# Addon_-_out8_16A_-_energy_storage_-_4TE_.net
KiCad netlist of a schematic drawn in EAGLE
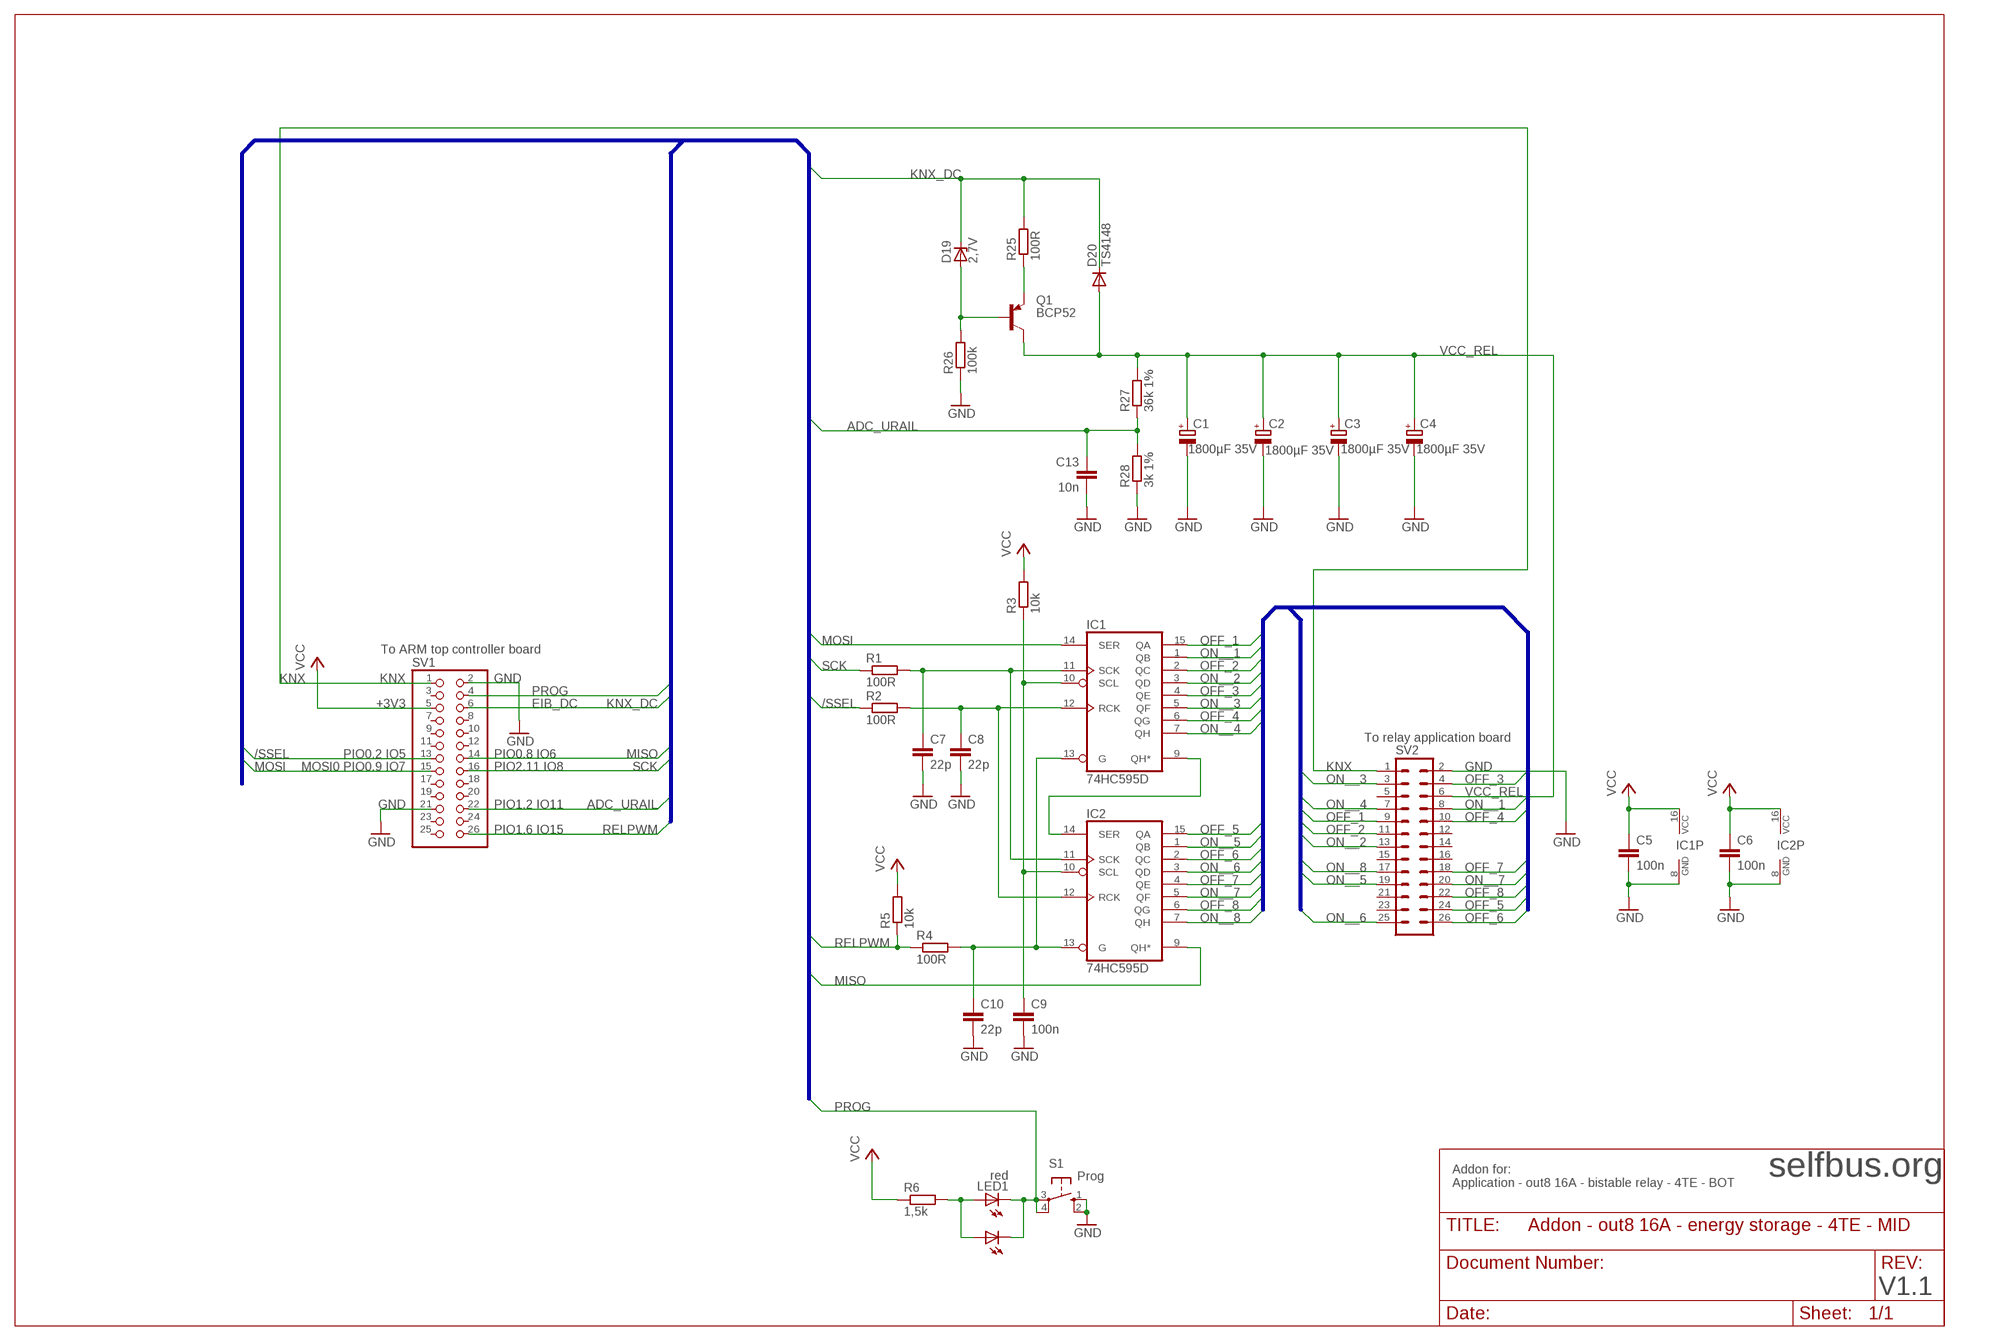
[diagram p0: schematic, sheet 1]

(export (version "E")
  (design (tool "Eeschema 10.0.6"))
  (components
    (comp (ref "C1")
      (value "1800µF 35V")
      (footprint "eagle-import:E5-13-30")
      (libsource (lib "eagle-import") (part "CPOL-EUE5-13-30"))
    )
    (comp (ref "C2")
      (value "1800µF 35V")
      (footprint "eagle-import:E5-13-30")
      (libsource (lib "eagle-import") (part "CPOL-EUE5-13-30"))
    )
    (comp (ref "C3")
      (value "1800µF 35V")
      (footprint "eagle-import:E5-13-30")
      (libsource (lib "eagle-import") (part "CPOL-EUE5-13-30"))
    )
    (comp (ref "C4")
      (value "1800µF 35V")
      (footprint "eagle-import:E5-13-30")
      (libsource (lib "eagle-import") (part "CPOL-EUE5-13-30"))
    )
    (comp (ref "C5")
      (value "100n")
      (footprint "eagle-import:R0805M")
      (libsource (lib "eagle-import") (part "C-EUC0805M"))
    )
    (comp (ref "C6")
      (value "100n")
      (footprint "eagle-import:R0805M")
      (libsource (lib "eagle-import") (part "C-EUC0805M"))
    )
    (comp (ref "C7")
      (value "22p")
      (footprint "eagle-import:R0805M")
      (libsource (lib "eagle-import") (part "C-EUC0805M"))
    )
    (comp (ref "C8")
      (value "22p")
      (footprint "eagle-import:R0805M")
      (libsource (lib "eagle-import") (part "C-EUC0805M"))
    )
    (comp (ref "C9")
      (value "100n")
      (footprint "eagle-import:R0805M")
      (libsource (lib "eagle-import") (part "C-EUC0805M"))
    )
    (comp (ref "C10")
      (value "22p")
      (footprint "eagle-import:R0805M")
      (libsource (lib "eagle-import") (part "C-EUC0805M"))
    )
    (comp (ref "C13")
      (value "10n")
      (footprint "eagle-import:R0805M")
      (libsource (lib "eagle-import") (part "C-EUC0805M"))
    )
    (comp (ref "D19")
      (value "2,7V")
      (footprint "eagle-import:SOT23")
      (libsource (lib "eagle-import") (part "ZENER-DIODESOT23"))
    )
    (comp (ref "D20")
      (value "TS4148")
      (footprint "eagle-import:D0805")
      (libsource (lib "eagle-import") (part "DIODE-D0805"))
    )
    (comp (ref "IC1")
      (value "74HC595D")
      (footprint "eagle-import:SO16")
      (libsource (lib "eagle-import") (part "74595DHC"))
    )
    (comp (ref "IC2")
      (value "74HC595D")
      (footprint "eagle-import:SO16")
      (libsource (lib "eagle-import") (part "74595DHC"))
    )
    (comp (ref "LED1")
      (value "red")
      (footprint "eagle-import:LED3MM")
      (libsource (lib "eagle-import") (part "LED3MM"))
    )
    (comp (ref "LED2")
      (value "LG_T679-E1F1-1")
      (footprint "eagle-import:PLCC2")
      (libsource (lib "eagle-import") (part "_T679-?-1E1F1LG"))
    )
    (comp (ref "Q1")
      (value "BCP52")
      (footprint "eagle-import:SOT223")
      (libsource (lib "eagle-import") (part "FZT753SMD"))
    )
    (comp (ref "R1")
      (value "100R")
      (footprint "eagle-import:R0805M")
      (libsource (lib "eagle-import") (part "R-EU_R0805M"))
    )
    (comp (ref "R2")
      (value "100R")
      (footprint "eagle-import:R0805M")
      (libsource (lib "eagle-import") (part "R-EU_R0805M"))
    )
    (comp (ref "R3")
      (value "10k")
      (footprint "eagle-import:R0805M")
      (libsource (lib "eagle-import") (part "R-EU_R0805M"))
    )
    (comp (ref "R4")
      (value "100R")
      (footprint "eagle-import:R0805M")
      (libsource (lib "eagle-import") (part "R-EU_R0805M"))
    )
    (comp (ref "R5")
      (value "10k")
      (footprint "eagle-import:R0805M")
      (libsource (lib "eagle-import") (part "R-EU_R0805M"))
    )
    (comp (ref "R6")
      (value "1,5k")
      (footprint "eagle-import:R0805M")
      (libsource (lib "eagle-import") (part "R-EU_R0805M"))
    )
    (comp (ref "R25")
      (value "100R")
      (footprint "eagle-import:R0805M")
      (libsource (lib "eagle-import") (part "R-EU_R0805M"))
    )
    (comp (ref "R26")
      (value "100k")
      (footprint "eagle-import:R0805M")
      (libsource (lib "eagle-import") (part "R-EU_R0805M"))
    )
    (comp (ref "R27")
      (value "36k 1%")
      (footprint "eagle-import:R0805M")
      (libsource (lib "eagle-import") (part "R-EU_R0805M"))
    )
    (comp (ref "R28")
      (value "3k 1%")
      (footprint "eagle-import:R0805M")
      (libsource (lib "eagle-import") (part "R-EU_R0805M"))
    )
    (comp (ref "S1")
      (value "Prog")
      (footprint "eagle-import:B3F-10XX")
      (libsource (lib "eagle-import") (part "10-XX"))
    )
    (comp (ref "SV1")
      (value "B")
      (footprint "eagle-import:2X13SMD")
      (libsource (lib "eagle-import") (part "PINHD-2X13SMD"))
    )
    (comp (ref "SV2")
      (value "A")
      (footprint "eagle-import:ML26")
      (libsource (lib "eagle-import") (part "ML26"))
    )
  )
  (nets
    (net (code "1") (name "/ADC_URAIL") (class "Default")
      (node (ref "C13") (pin "1") (pinfunction "1_1") (pintype "passive"))
      (node (ref "R27") (pin "1") (pinfunction "1_1") (pintype "passive"))
      (node (ref "R28") (pin "2") (pinfunction "2_2") (pintype "passive"))
      (node (ref "SV1") (pin "22") (pinfunction "22_22") (pintype "passive"))
    )
    (net (code "2") (name "/KNX") (class "Default")
      (node (ref "SV1") (pin "1") (pinfunction "1_1") (pintype "passive"))
      (node (ref "SV2") (pin "1") (pinfunction "1_1") (pintype "passive"))
    )
    (net (code "3") (name "/KNX_DC") (class "Default")
      (node (ref "D19") (pin "3") (pinfunction "C_3") (pintype "passive"))
      (node (ref "D20") (pin "C") (pinfunction "C_C") (pintype "passive"))
      (node (ref "R25") (pin "2") (pinfunction "2_2") (pintype "passive"))
      (node (ref "SV1") (pin "6") (pinfunction "6_6") (pintype "passive"))
    )
    (net (code "4") (name "/MISO") (class "Default")
      (node (ref "IC2") (pin "9") (pinfunction "QH*_9") (pintype "tri_state"))
      (node (ref "SV1") (pin "14") (pinfunction "14_14") (pintype "passive"))
    )
    (net (code "5") (name "/MOSI") (class "Default")
      (node (ref "IC1") (pin "14") (pinfunction "SER_14") (pintype "input"))
      (node (ref "SV1") (pin "15") (pinfunction "15_15") (pintype "passive"))
    )
    (net (code "6") (name "/OFF_1") (class "Default")
      (node (ref "IC1") (pin "15") (pinfunction "QA_15") (pintype "tri_state"))
      (node (ref "SV2") (pin "9") (pinfunction "9_9") (pintype "passive"))
    )
    (net (code "7") (name "/OFF_2") (class "Default")
      (node (ref "IC1") (pin "2") (pinfunction "QC_2") (pintype "tri_state"))
      (node (ref "SV2") (pin "11") (pinfunction "11_11") (pintype "passive"))
    )
    (net (code "8") (name "/OFF_3") (class "Default")
      (node (ref "IC1") (pin "4") (pinfunction "QE_4") (pintype "tri_state"))
      (node (ref "SV2") (pin "4") (pinfunction "4_4") (pintype "passive"))
    )
    (net (code "9") (name "/OFF_4") (class "Default")
      (node (ref "IC1") (pin "6") (pinfunction "QG_6") (pintype "tri_state"))
      (node (ref "SV2") (pin "10") (pinfunction "10_10") (pintype "passive"))
    )
    (net (code "10") (name "/OFF_5") (class "Default")
      (node (ref "IC2") (pin "15") (pinfunction "QA_15") (pintype "tri_state"))
      (node (ref "SV2") (pin "24") (pinfunction "24_24") (pintype "passive"))
    )
    (net (code "11") (name "/OFF_6") (class "Default")
      (node (ref "IC2") (pin "2") (pinfunction "QC_2") (pintype "tri_state"))
      (node (ref "SV2") (pin "26") (pinfunction "26_26") (pintype "passive"))
    )
    (net (code "12") (name "/OFF_7") (class "Default")
      (node (ref "IC2") (pin "4") (pinfunction "QE_4") (pintype "tri_state"))
      (node (ref "SV2") (pin "18") (pinfunction "18_18") (pintype "passive"))
    )
    (net (code "13") (name "/OFF_8") (class "Default")
      (node (ref "IC2") (pin "6") (pinfunction "QG_6") (pintype "tri_state"))
      (node (ref "SV2") (pin "22") (pinfunction "22_22") (pintype "passive"))
    )
    (net (code "14") (name "/ON__1") (class "Default")
      (node (ref "IC1") (pin "1") (pinfunction "QB_1") (pintype "tri_state"))
      (node (ref "SV2") (pin "8") (pinfunction "8_8") (pintype "passive"))
    )
    (net (code "15") (name "/ON__2") (class "Default")
      (node (ref "IC1") (pin "3") (pinfunction "QD_3") (pintype "tri_state"))
      (node (ref "SV2") (pin "13") (pinfunction "13_13") (pintype "passive"))
    )
    (net (code "16") (name "/ON__3") (class "Default")
      (node (ref "IC1") (pin "5") (pinfunction "QF_5") (pintype "tri_state"))
      (node (ref "SV2") (pin "3") (pinfunction "3_3") (pintype "passive"))
    )
    (net (code "17") (name "/ON__4") (class "Default")
      (node (ref "IC1") (pin "7") (pinfunction "QH_7") (pintype "tri_state"))
      (node (ref "SV2") (pin "7") (pinfunction "7_7") (pintype "passive"))
    )
    (net (code "18") (name "/ON__5") (class "Default")
      (node (ref "IC2") (pin "1") (pinfunction "QB_1") (pintype "tri_state"))
      (node (ref "SV2") (pin "19") (pinfunction "19_19") (pintype "passive"))
    )
    (net (code "19") (name "/ON__6") (class "Default")
      (node (ref "IC2") (pin "3") (pinfunction "QD_3") (pintype "tri_state"))
      (node (ref "SV2") (pin "25") (pinfunction "25_25") (pintype "passive"))
    )
    (net (code "20") (name "/ON__7") (class "Default")
      (node (ref "IC2") (pin "5") (pinfunction "QF_5") (pintype "tri_state"))
      (node (ref "SV2") (pin "20") (pinfunction "20_20") (pintype "passive"))
    )
    (net (code "21") (name "/ON__8") (class "Default")
      (node (ref "IC2") (pin "7") (pinfunction "QH_7") (pintype "tri_state"))
      (node (ref "SV2") (pin "17") (pinfunction "17_17") (pintype "passive"))
    )
    (net (code "22") (name "/PROG") (class "Default")
      (node (ref "LED1") (pin "K") (pinfunction "C_K") (pintype "passive"))
      (node (ref "LED2") (pin "C") (pinfunction "C_C") (pintype "passive"))
      (node (ref "S1") (pin "3") (pinfunction "P_3") (pintype "passive"))
      (node (ref "S1") (pin "4") (pinfunction "P1_4") (pintype "passive"))
      (node (ref "SV1") (pin "4") (pinfunction "4_4") (pintype "passive"))
    )
    (net (code "23") (name "/RELPWM") (class "Default")
      (node (ref "R4") (pin "1") (pinfunction "1_1") (pintype "passive"))
      (node (ref "R5") (pin "1") (pinfunction "1_1") (pintype "passive"))
      (node (ref "SV1") (pin "26") (pinfunction "26_26") (pintype "passive"))
    )
    (net (code "24") (name "/SCK") (class "Default")
      (node (ref "R1") (pin "1") (pinfunction "1_1") (pintype "passive"))
      (node (ref "SV1") (pin "16") (pinfunction "16_16") (pintype "passive"))
    )
    (net (code "25") (name "/VCC_REL") (class "Default")
      (node (ref "C1") (pin "+") (pinfunction "+_+") (pintype "passive"))
      (node (ref "C2") (pin "+") (pinfunction "+_+") (pintype "passive"))
      (node (ref "C3") (pin "+") (pinfunction "+_+") (pintype "passive"))
      (node (ref "C4") (pin "+") (pinfunction "+_+") (pintype "passive"))
      (node (ref "D20") (pin "A") (pinfunction "A_A") (pintype "passive"))
      (node (ref "Q1") (pin "2") (pinfunction "C_2") (pintype "passive"))
      (node (ref "Q1") (pin "4") (pinfunction "C_4") (pintype "passive"))
      (node (ref "R27") (pin "2") (pinfunction "2_2") (pintype "passive"))
      (node (ref "SV2") (pin "6") (pinfunction "6_6") (pintype "passive"))
    )
    (net (code "26") (name "/{slash}SSEL") (class "Default")
      (node (ref "R2") (pin "1") (pinfunction "1_1") (pintype "passive"))
      (node (ref "SV1") (pin "13") (pinfunction "13_13") (pintype "passive"))
    )
    (net (code "27") (name "GND") (class "Default")
      (node (ref "C1") (pin "-") (pinfunction "-_-") (pintype "passive"))
      (node (ref "C10") (pin "2") (pinfunction "2_2") (pintype "passive"))
      (node (ref "C13") (pin "2") (pinfunction "2_2") (pintype "passive"))
      (node (ref "C2") (pin "-") (pinfunction "-_-") (pintype "passive"))
      (node (ref "C3") (pin "-") (pinfunction "-_-") (pintype "passive"))
      (node (ref "C4") (pin "-") (pinfunction "-_-") (pintype "passive"))
      (node (ref "C5") (pin "2") (pinfunction "2_2") (pintype "passive"))
      (node (ref "C6") (pin "2") (pinfunction "2_2") (pintype "passive"))
      (node (ref "C7") (pin "2") (pinfunction "2_2") (pintype "passive"))
      (node (ref "C8") (pin "2") (pinfunction "2_2") (pintype "passive"))
      (node (ref "C9") (pin "2") (pinfunction "2_2") (pintype "passive"))
      (node (ref "IC1") (pin "8") (pinfunction "GND_8") (pintype "power_in"))
      (node (ref "IC2") (pin "8") (pinfunction "GND_8") (pintype "power_in"))
      (node (ref "R26") (pin "1") (pinfunction "1_1") (pintype "passive"))
      (node (ref "R28") (pin "1") (pinfunction "1_1") (pintype "passive"))
      (node (ref "S1") (pin "1") (pinfunction "S_1") (pintype "passive"))
      (node (ref "S1") (pin "2") (pinfunction "S1_2") (pintype "passive"))
      (node (ref "SV1") (pin "2") (pinfunction "2_2") (pintype "passive"))
      (node (ref "SV1") (pin "21") (pinfunction "21_21") (pintype "passive"))
      (node (ref "SV2") (pin "2") (pinfunction "2_2") (pintype "passive"))
    )
    (net (code "28") (name "Net-(D19-A)") (class "Default")
      (node (ref "D19") (pin "1") (pinfunction "A_1") (pintype "passive"))
      (node (ref "Q1") (pin "1") (pinfunction "B_1") (pintype "passive"))
      (node (ref "R26") (pin "2") (pinfunction "2_2") (pintype "passive"))
    )
    (net (code "29") (name "Net-(IC1A-G)") (class "Default")
      (node (ref "C10") (pin "1") (pinfunction "1_1") (pintype "passive"))
      (node (ref "IC1") (pin "13") (pinfunction "G_13") (pintype "input"))
      (node (ref "IC2") (pin "13") (pinfunction "G_13") (pintype "input"))
      (node (ref "R4") (pin "2") (pinfunction "2_2") (pintype "passive"))
    )
    (net (code "30") (name "Net-(IC1A-QH*)") (class "Default")
      (node (ref "IC1") (pin "9") (pinfunction "QH*_9") (pintype "tri_state"))
      (node (ref "IC2") (pin "14") (pinfunction "SER_14") (pintype "input"))
    )
    (net (code "31") (name "Net-(IC1A-RCK)") (class "Default")
      (node (ref "C8") (pin "1") (pinfunction "1_1") (pintype "passive"))
      (node (ref "IC1") (pin "12") (pinfunction "RCK_12") (pintype "input"))
      (node (ref "IC2") (pin "12") (pinfunction "RCK_12") (pintype "input"))
      (node (ref "R2") (pin "2") (pinfunction "2_2") (pintype "passive"))
    )
    (net (code "32") (name "Net-(IC1A-SCK)") (class "Default")
      (node (ref "C7") (pin "1") (pinfunction "1_1") (pintype "passive"))
      (node (ref "IC1") (pin "11") (pinfunction "SCK_11") (pintype "input"))
      (node (ref "IC2") (pin "11") (pinfunction "SCK_11") (pintype "input"))
      (node (ref "R1") (pin "2") (pinfunction "2_2") (pintype "passive"))
    )
    (net (code "33") (name "Net-(IC1A-SCL)") (class "Default")
      (node (ref "C9") (pin "1") (pinfunction "1_1") (pintype "passive"))
      (node (ref "IC1") (pin "10") (pinfunction "SCL_10") (pintype "input"))
      (node (ref "IC2") (pin "10") (pinfunction "SCL_10") (pintype "input"))
      (node (ref "R3") (pin "1") (pinfunction "1_1") (pintype "passive"))
    )
    (net (code "34") (name "Net-(LED1-PadA)") (class "Default")
      (node (ref "LED1") (pin "A") (pinfunction "A_A") (pintype "passive"))
      (node (ref "LED2") (pin "A") (pinfunction "A_A") (pintype "passive"))
      (node (ref "R6") (pin "2") (pinfunction "2_2") (pintype "passive"))
    )
    (net (code "35") (name "Net-(Q1-E)") (class "Default")
      (node (ref "Q1") (pin "3") (pinfunction "E_3") (pintype "passive"))
      (node (ref "R25") (pin "1") (pinfunction "1_1") (pintype "passive"))
    )
    (net (code "36") (name "VCC") (class "Default")
      (node (ref "C5") (pin "1") (pinfunction "1_1") (pintype "passive"))
      (node (ref "C6") (pin "1") (pinfunction "1_1") (pintype "passive"))
      (node (ref "IC1") (pin "16") (pinfunction "VCC_16") (pintype "power_in"))
      (node (ref "IC2") (pin "16") (pinfunction "VCC_16") (pintype "power_in"))
      (node (ref "R3") (pin "2") (pinfunction "2_2") (pintype "passive"))
      (node (ref "R5") (pin "2") (pinfunction "2_2") (pintype "passive"))
      (node (ref "R6") (pin "1") (pinfunction "1_1") (pintype "passive"))
      (node (ref "SV1") (pin "5") (pinfunction "5_5") (pintype "passive"))
    )
    (net (code "37") (name "unconnected-(SV1-Pad3)") (class "Default")
      (node (ref "SV1") (pin "3") (pinfunction "3_3") (pintype "passive"))
    )
    (net (code "38") (name "unconnected-(SV1-Pad7)") (class "Default")
      (node (ref "SV1") (pin "7") (pinfunction "7_7") (pintype "passive"))
    )
    (net (code "39") (name "unconnected-(SV1-Pad8)") (class "Default")
      (node (ref "SV1") (pin "8") (pinfunction "8_8") (pintype "passive"))
    )
    (net (code "40") (name "unconnected-(SV1-Pad9)") (class "Default")
      (node (ref "SV1") (pin "9") (pinfunction "9_9") (pintype "passive"))
    )
    (net (code "41") (name "unconnected-(SV1-Pad10)") (class "Default")
      (node (ref "SV1") (pin "10") (pinfunction "10_10") (pintype "passive"))
    )
    (net (code "42") (name "unconnected-(SV1-Pad11)") (class "Default")
      (node (ref "SV1") (pin "11") (pinfunction "11_11") (pintype "passive"))
    )
    (net (code "43") (name "unconnected-(SV1-Pad12)") (class "Default")
      (node (ref "SV1") (pin "12") (pinfunction "12_12") (pintype "passive"))
    )
    (net (code "44") (name "unconnected-(SV1-Pad17)") (class "Default")
      (node (ref "SV1") (pin "17") (pinfunction "17_17") (pintype "passive"))
    )
    (net (code "45") (name "unconnected-(SV1-Pad18)") (class "Default")
      (node (ref "SV1") (pin "18") (pinfunction "18_18") (pintype "passive"))
    )
    (net (code "46") (name "unconnected-(SV1-Pad19)") (class "Default")
      (node (ref "SV1") (pin "19") (pinfunction "19_19") (pintype "passive"))
    )
    (net (code "47") (name "unconnected-(SV1-Pad20)") (class "Default")
      (node (ref "SV1") (pin "20") (pinfunction "20_20") (pintype "passive"))
    )
    (net (code "48") (name "unconnected-(SV1-Pad23)") (class "Default")
      (node (ref "SV1") (pin "23") (pinfunction "23_23") (pintype "passive"))
    )
    (net (code "49") (name "unconnected-(SV1-Pad24)") (class "Default")
      (node (ref "SV1") (pin "24") (pinfunction "24_24") (pintype "passive"))
    )
    (net (code "50") (name "unconnected-(SV1-Pad25)") (class "Default")
      (node (ref "SV1") (pin "25") (pinfunction "25_25") (pintype "passive"))
    )
    (net (code "51") (name "unconnected-(SV2-Pad5)") (class "Default")
      (node (ref "SV2") (pin "5") (pinfunction "5_5") (pintype "passive"))
    )
    (net (code "52") (name "unconnected-(SV2-Pad12)") (class "Default")
      (node (ref "SV2") (pin "12") (pinfunction "12_12") (pintype "passive"))
    )
    (net (code "53") (name "unconnected-(SV2-Pad14)") (class "Default")
      (node (ref "SV2") (pin "14") (pinfunction "14_14") (pintype "passive"))
    )
    (net (code "54") (name "unconnected-(SV2-Pad15)") (class "Default")
      (node (ref "SV2") (pin "15") (pinfunction "15_15") (pintype "passive"))
    )
    (net (code "55") (name "unconnected-(SV2-Pad16)") (class "Default")
      (node (ref "SV2") (pin "16") (pinfunction "16_16") (pintype "passive"))
    )
    (net (code "56") (name "unconnected-(SV2-Pad21)") (class "Default")
      (node (ref "SV2") (pin "21") (pinfunction "21_21") (pintype "passive"))
    )
    (net (code "57") (name "unconnected-(SV2-Pad23)") (class "Default")
      (node (ref "SV2") (pin "23") (pinfunction "23_23") (pintype "passive"))
    )
  )
)
